# OC_PROT.net
KiCad netlist of a schematic drawn in Altium Designer
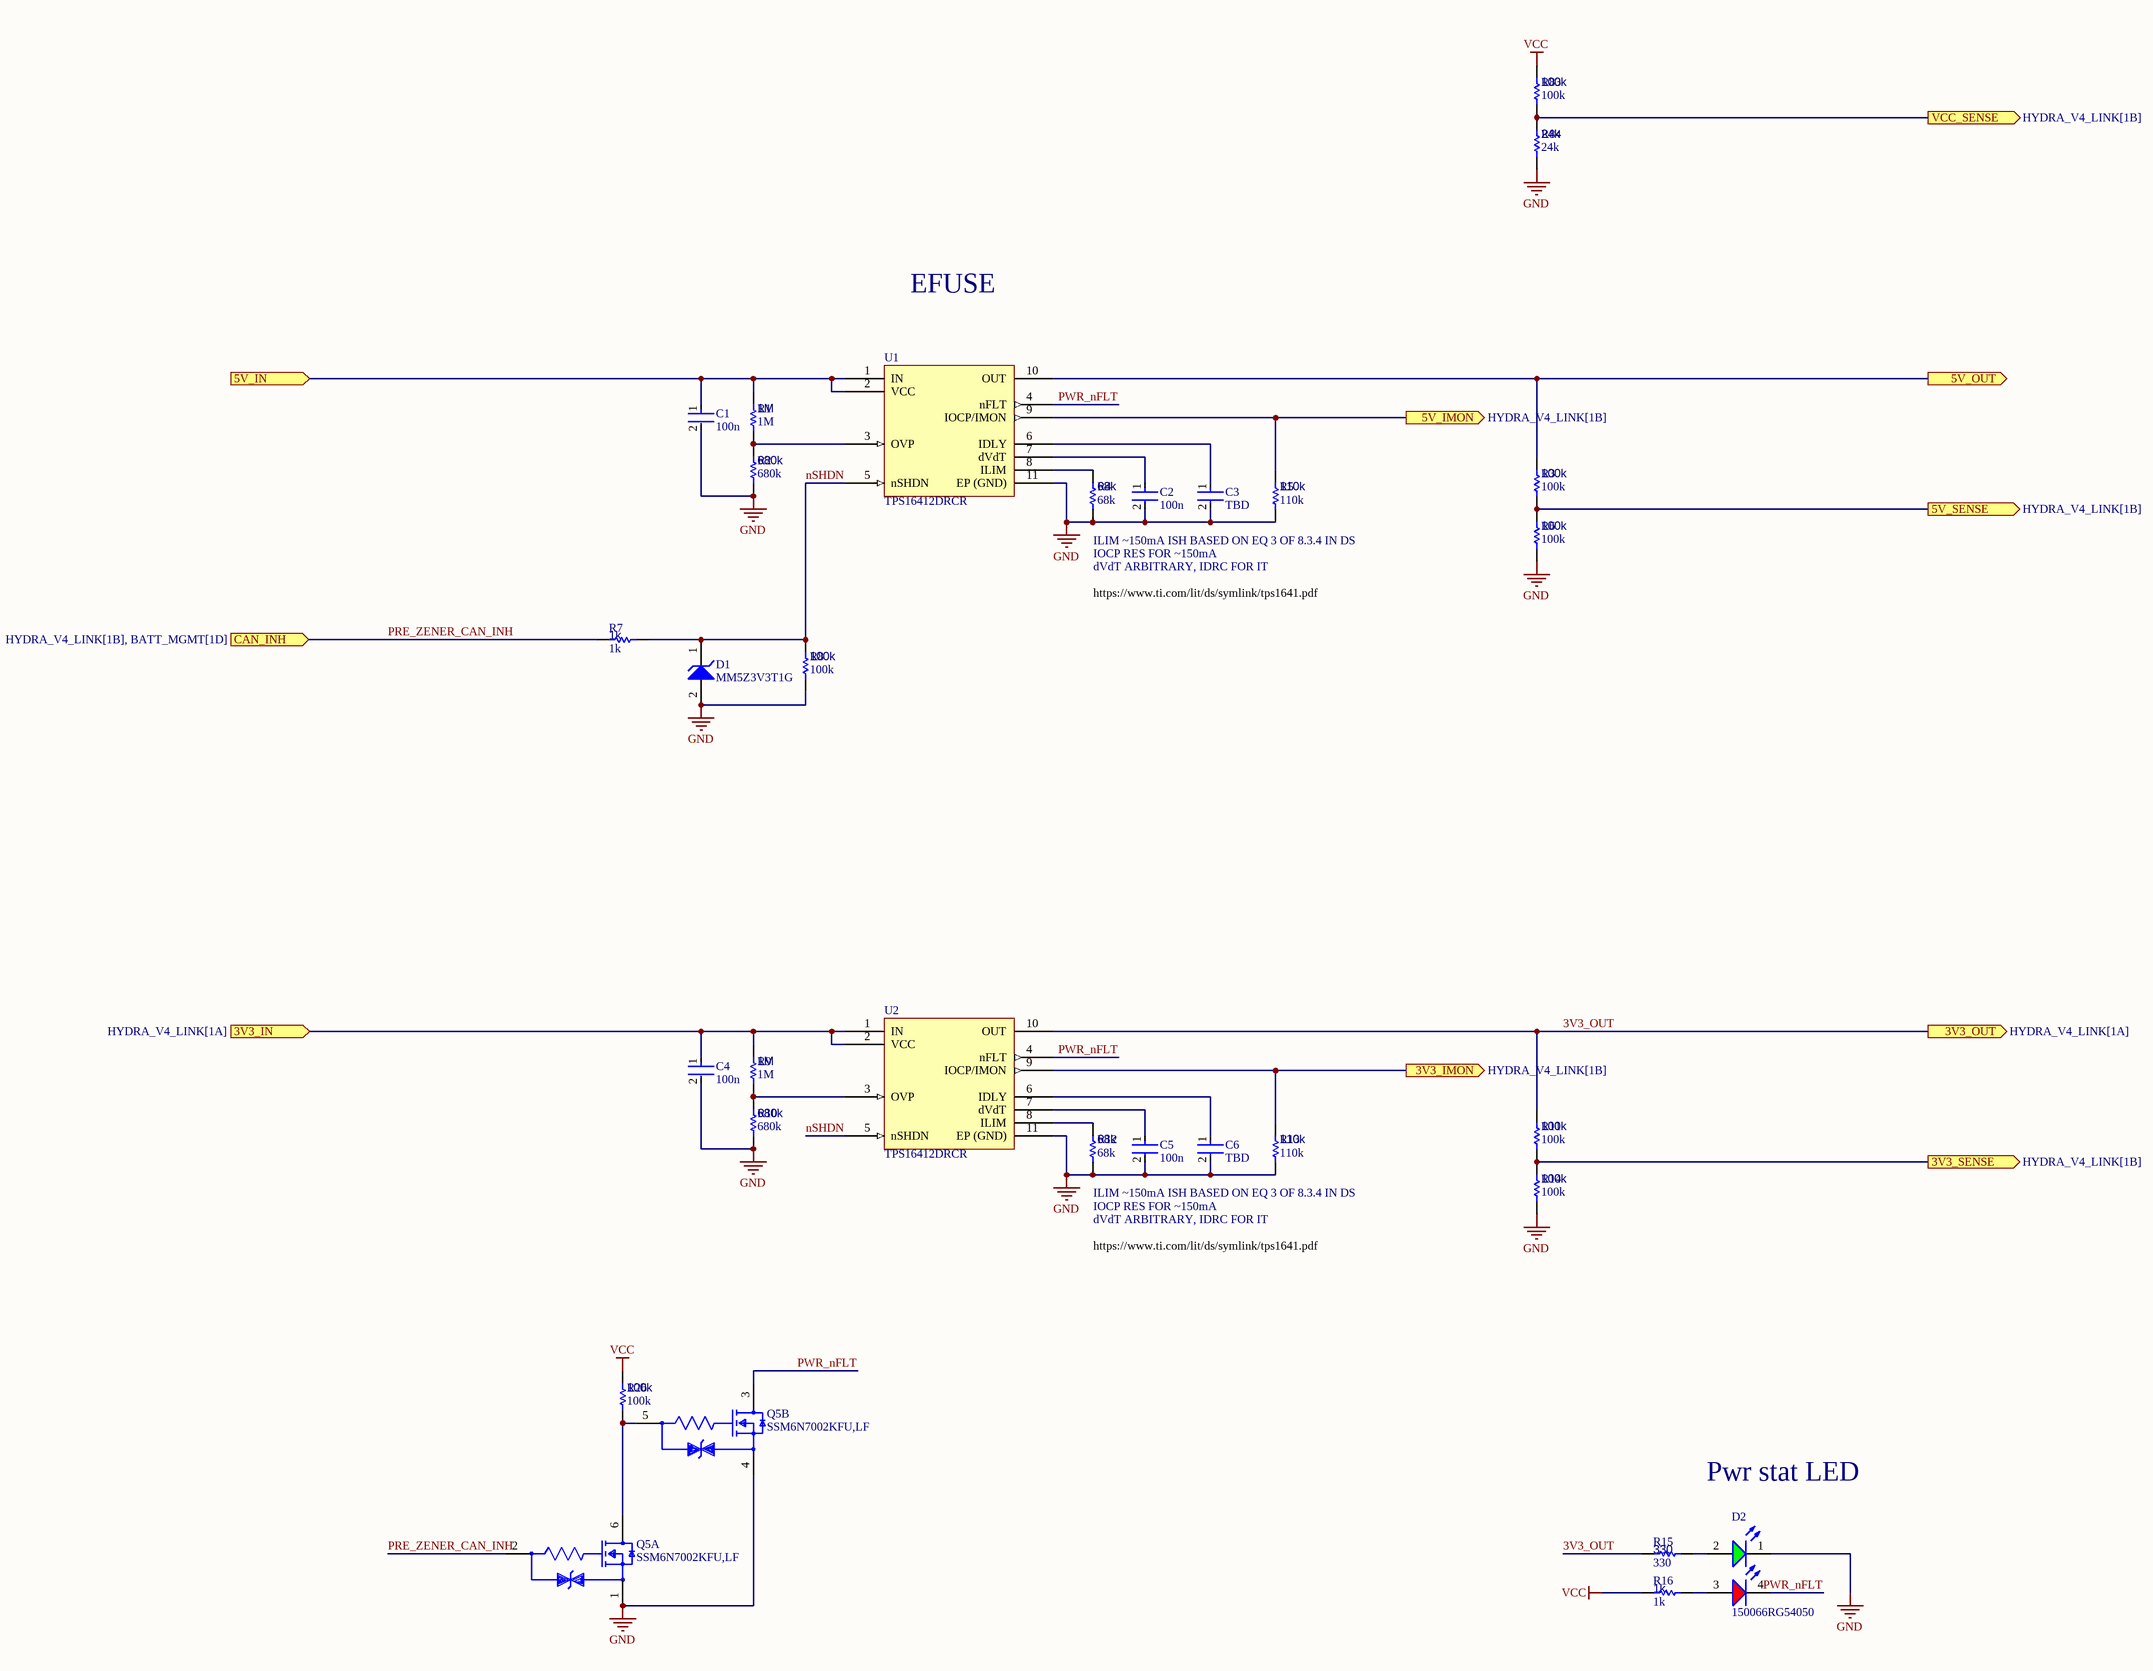
[diagram p0: OC_PROT.SchDoc]

(export (version "E")
  (design (tool "Eeschema 10.0.6"))
  (components
    (comp (ref "C1")
      (value "100n")
      (footprint "FP-0402-L_1_0_0_05-W_0_5-IPC_A")
      (description "LARGE PADS, 0402 CAP, CHANGE COMMENT TO MATCH REAL P/N")
      (libsource (lib "Space Concordia") (part "b4654b650e69147ec39a6b967a45e02"))
    )
    (comp (ref "C2")
      (value "100n")
      (footprint "FP-0402-L_1_0_0_05-W_0_5-IPC_A")
      (description "LARGE PADS, 0402 CAP, CHANGE COMMENT TO MATCH REAL P/N")
      (libsource (lib "Space Concordia") (part "b4654b650e69147ec39a6b967a45e02"))
    )
    (comp (ref "C3")
      (value "TBD")
      (footprint "FP-0402-L_1_0_0_05-W_0_5-IPC_A")
      (description "LARGE PADS, 0402 CAP, CHANGE COMMENT TO MATCH REAL P/N")
      (libsource (lib "Space Concordia") (part "b4654b650e69147ec39a6b967a45e02"))
    )
    (comp (ref "C4")
      (value "100n")
      (footprint "FP-0402-L_1_0_0_05-W_0_5-IPC_A")
      (description "LARGE PADS, 0402 CAP, CHANGE COMMENT TO MATCH REAL P/N")
      (libsource (lib "Space Concordia") (part "b4654b650e69147ec39a6b967a45e02"))
    )
    (comp (ref "C5")
      (value "100n")
      (footprint "FP-0402-L_1_0_0_05-W_0_5-IPC_A")
      (description "LARGE PADS, 0402 CAP, CHANGE COMMENT TO MATCH REAL P/N")
      (libsource (lib "Space Concordia") (part "b4654b650e69147ec39a6b967a45e02"))
    )
    (comp (ref "C6")
      (value "TBD")
      (footprint "FP-0402-L_1_0_0_05-W_0_5-IPC_A")
      (description "LARGE PADS, 0402 CAP, CHANGE COMMENT TO MATCH REAL P/N")
      (libsource (lib "Space Concordia") (part "b4654b650e69147ec39a6b967a45e02"))
    )
    (comp (ref "D1")
      (value "MM5Z3V3T1G")
      (footprint "ONSC-SOD-523-2-502-01_V")
      (description "Zener Voltage Regulator, 500 mW, 2-Pin SOD-523, Pb-Free, Tape and Reel")
      (fields (field (name "MANUFACTURER") "On Semiconductor"))
      (libsource (lib "Altium Content Vault") (part "ONSC-K1A2-2"))
    )
    (comp (ref "D2")
      (value "150066RG54050")
      (footprint "WL-SBCD_0606")
      (description "Led, Red/Grn, 180Mcd/230Mcd, 624Nm/525Nm Rohs Compliant: Yes")
      (fields (field (name "SOURCE") "rgled.SchLib"))
      (libsource (lib "Space Concordia") (part "CMP-004-00034-2"))
    )
    (comp (ref "Q5")
      (value "SSM6N7002KFU,LF")
      (footprint "FP-SSOP6-P-0_65A-MFG")
      (description "Transistor MOSFET Array Dual N-CH 60V 300mA 6-Pin SOT-363 Emboss T/R")
      (libsource (lib "Space Concordia") (part "088aa6ac103fdeebe0d1c52ece6b7b9"))
    )
    (comp (ref "R1")
      (value "1M")
      (footprint "R0603B")
      (description "Resistor")
      (fields (field (name "ALTIUM_VALUE") "1M"))
      (libsource (lib "Space Concordia") (part "Resistor"))
    )
    (comp (ref "R2")
      (value "680k")
      (footprint "R0603B")
      (description "Resistor")
      (fields (field (name "ALTIUM_VALUE") "680k"))
      (libsource (lib "Space Concordia") (part "Resistor"))
    )
    (comp (ref "R3")
      (value "100k")
      (footprint "R0603B")
      (description "Resistor")
      (fields (field (name "ALTIUM_VALUE") "100k"))
      (libsource (lib "Space Concordia") (part "Resistor"))
    )
    (comp (ref "R4")
      (value "68k")
      (footprint "R0603B")
      (description "Resistor")
      (fields (field (name "ALTIUM_VALUE") "68k"))
      (libsource (lib "Space Concordia") (part "Resistor"))
    )
    (comp (ref "R5")
      (value "110k")
      (footprint "R0603B")
      (description "Resistor")
      (fields (field (name "ALTIUM_VALUE") "110k"))
      (libsource (lib "Space Concordia") (part "Resistor"))
    )
    (comp (ref "R6")
      (value "100k")
      (footprint "R0603B")
      (description "Resistor")
      (fields (field (name "ALTIUM_VALUE") "100k"))
      (libsource (lib "Space Concordia") (part "Resistor"))
    )
    (comp (ref "R7")
      (value "1k")
      (footprint "R0603B")
      (description "Resistor")
      (fields (field (name "ALTIUM_VALUE") "1k"))
      (libsource (lib "Space Concordia") (part "Resistor"))
    )
    (comp (ref "R8")
      (value "100k")
      (footprint "R0603B")
      (description "Resistor")
      (fields (field (name "ALTIUM_VALUE") "100k"))
      (libsource (lib "Space Concordia") (part "Resistor"))
    )
    (comp (ref "R9")
      (value "1M")
      (footprint "R0603B")
      (description "Resistor")
      (fields (field (name "ALTIUM_VALUE") "1M"))
      (libsource (lib "Space Concordia") (part "Resistor"))
    )
    (comp (ref "R10")
      (value "680k")
      (footprint "R0603B")
      (description "Resistor")
      (fields (field (name "ALTIUM_VALUE") "680k"))
      (libsource (lib "Space Concordia") (part "Resistor"))
    )
    (comp (ref "R11")
      (value "100k")
      (footprint "R0603B")
      (description "Resistor")
      (fields (field (name "ALTIUM_VALUE") "100k"))
      (libsource (lib "Space Concordia") (part "Resistor"))
    )
    (comp (ref "R12")
      (value "68k")
      (footprint "R0603B")
      (description "Resistor")
      (fields (field (name "ALTIUM_VALUE") "68k"))
      (libsource (lib "Space Concordia") (part "Resistor"))
    )
    (comp (ref "R13")
      (value "110k")
      (footprint "R0603B")
      (description "Resistor")
      (fields (field (name "ALTIUM_VALUE") "110k"))
      (libsource (lib "Space Concordia") (part "Resistor"))
    )
    (comp (ref "R14")
      (value "100k")
      (footprint "R0603B")
      (description "Resistor")
      (fields (field (name "ALTIUM_VALUE") "100k"))
      (libsource (lib "Space Concordia") (part "Resistor"))
    )
    (comp (ref "R15")
      (value "330")
      (footprint "R0603B")
      (description "Resistor")
      (fields (field (name "ALTIUM_VALUE") "330"))
      (libsource (lib "Space Concordia") (part "Resistor"))
    )
    (comp (ref "R16")
      (value "1k")
      (footprint "R0603B")
      (description "Resistor")
      (fields (field (name "ALTIUM_VALUE") "1k"))
      (libsource (lib "Space Concordia") (part "Resistor"))
    )
    (comp (ref "R26")
      (value "100k")
      (footprint "R0603B")
      (description "Resistor")
      (fields (field (name "ALTIUM_VALUE") "100k"))
      (libsource (lib "Space Concordia") (part "Resistor"))
    )
    (comp (ref "R83")
      (value "100k")
      (footprint "R0603B")
      (description "Resistor")
      (fields (field (name "ALTIUM_VALUE") "100k"))
      (libsource (lib "Space Concordia") (part "Resistor"))
    )
    (comp (ref "R84")
      (value "24k")
      (footprint "R0603B")
      (description "Resistor")
      (fields (field (name "ALTIUM_VALUE") "24k"))
      (libsource (lib "Space Concordia") (part "Resistor"))
    )
    (comp (ref "U1")
      (value "TPS16412DRCR")
      (footprint "PSON50P300X100_HS-11N")
      (description "2.7-V to 40-V 152-mΩ 1.8-A eFuse with output power limiting 10-VSON -40 to 125")
      (libsource (lib "Space Concordia") (part "TPS16412DRCR"))
    )
    (comp (ref "U2")
      (value "TPS16412DRCR")
      (footprint "PSON50P300X100_HS-11N")
      (description "2.7-V to 40-V 152-mΩ 1.8-A eFuse with output power limiting 10-VSON -40 to 125")
      (libsource (lib "Space Concordia") (part "TPS16412DRCR"))
    )
  )
  (nets
    (net (code "1") (name "/3V3_IMON") (class "Default")
      (node (ref "R13") (pin "1") (pinfunction "1_1") (pintype "passive"))
      (node (ref "U2") (pin "9") (pinfunction "IOCP/IMON_9") (pintype "output"))
    )
    (net (code "2") (name "/3V3_IN") (class "Default")
      (node (ref "C4") (pin "1") (pinfunction "1_1") (pintype "passive"))
      (node (ref "R9") (pin "1") (pinfunction "1_1") (pintype "passive"))
      (node (ref "U2") (pin "1") (pinfunction "IN_1") (pintype "power_in"))
      (node (ref "U2") (pin "2") (pinfunction "VCC_2") (pintype "power_in"))
    )
    (net (code "3") (name "/3V3_OUT") (class "Default")
      (node (ref "R11") (pin "2") (pinfunction "2_2") (pintype "passive"))
      (node (ref "R15") (pin "1") (pinfunction "1_1") (pintype "passive"))
      (node (ref "U2") (pin "10") (pinfunction "OUT_10") (pintype "power_in"))
    )
    (net (code "4") (name "/3V3_SENSE") (class "Default")
      (node (ref "R11") (pin "1") (pinfunction "1_1") (pintype "passive"))
      (node (ref "R14") (pin "2") (pinfunction "2_2") (pintype "passive"))
    )
    (net (code "5") (name "/5V_IMON") (class "Default")
      (node (ref "R5") (pin "1") (pinfunction "1_1") (pintype "passive"))
      (node (ref "U1") (pin "9") (pinfunction "IOCP/IMON_9") (pintype "output"))
    )
    (net (code "6") (name "/5V_IN") (class "Default")
      (node (ref "C1") (pin "1") (pinfunction "1_1") (pintype "passive"))
      (node (ref "R1") (pin "1") (pinfunction "1_1") (pintype "passive"))
      (node (ref "U1") (pin "1") (pinfunction "IN_1") (pintype "power_in"))
      (node (ref "U1") (pin "2") (pinfunction "VCC_2") (pintype "power_in"))
    )
    (net (code "7") (name "/5V_OUT") (class "Default")
      (node (ref "R3") (pin "2") (pinfunction "2_2") (pintype "passive"))
      (node (ref "U1") (pin "10") (pinfunction "OUT_10") (pintype "power_in"))
    )
    (net (code "8") (name "/5V_SENSE") (class "Default")
      (node (ref "R3") (pin "1") (pinfunction "1_1") (pintype "passive"))
      (node (ref "R6") (pin "2") (pinfunction "2_2") (pintype "passive"))
    )
    (net (code "9") (name "/PRE_ZENER_CAN_INH") (class "Default")
      (node (ref "Q5") (pin "2") (pinfunction "Gate1_2") (pintype "passive"))
      (node (ref "R7") (pin "2") (pinfunction "2_2") (pintype "passive"))
    )
    (net (code "10") (name "/PWR_nFLT") (class "Default")
      (node (ref "D2") (pin "4") (pinfunction "K_4") (pintype "passive"))
      (node (ref "Q5") (pin "3") (pinfunction "Drain2_3") (pintype "passive"))
      (node (ref "U1") (pin "4") (pinfunction "nFLT_4") (pintype "output"))
      (node (ref "U2") (pin "4") (pinfunction "nFLT_4") (pintype "output"))
    )
    (net (code "11") (name "/VCC_SENSE") (class "Default")
      (node (ref "R83") (pin "1") (pinfunction "1_1") (pintype "passive"))
      (node (ref "R84") (pin "2") (pinfunction "2_2") (pintype "passive"))
    )
    (net (code "12") (name "/nSHDN") (class "Default")
      (node (ref "D1") (pin "1") (pinfunction "K_1") (pintype "passive"))
      (node (ref "R7") (pin "1") (pinfunction "1_1") (pintype "passive"))
      (node (ref "R8") (pin "2") (pinfunction "2_2") (pintype "passive"))
      (node (ref "U1") (pin "5") (pinfunction "nSHDN_5") (pintype "input"))
      (node (ref "U2") (pin "5") (pinfunction "nSHDN_5") (pintype "input"))
    )
    (net (code "13") (name "GND") (class "Default")
      (node (ref "C1") (pin "2") (pinfunction "2_2") (pintype "passive"))
      (node (ref "C2") (pin "2") (pinfunction "2_2") (pintype "passive"))
      (node (ref "C3") (pin "2") (pinfunction "2_2") (pintype "passive"))
      (node (ref "C4") (pin "2") (pinfunction "2_2") (pintype "passive"))
      (node (ref "C5") (pin "2") (pinfunction "2_2") (pintype "passive"))
      (node (ref "C6") (pin "2") (pinfunction "2_2") (pintype "passive"))
      (node (ref "D1") (pin "2") (pinfunction "A_2") (pintype "passive"))
      (node (ref "D2") (pin "1") (pinfunction "K_1") (pintype "passive"))
      (node (ref "Q5") (pin "1") (pinfunction "Source1_1") (pintype "passive"))
      (node (ref "Q5") (pin "4") (pinfunction "Source2_4") (pintype "passive"))
      (node (ref "R10") (pin "2") (pinfunction "2_2") (pintype "passive"))
      (node (ref "R12") (pin "2") (pinfunction "2_2") (pintype "passive"))
      (node (ref "R13") (pin "2") (pinfunction "2_2") (pintype "passive"))
      (node (ref "R14") (pin "1") (pinfunction "1_1") (pintype "passive"))
      (node (ref "R2") (pin "2") (pinfunction "2_2") (pintype "passive"))
      (node (ref "R4") (pin "2") (pinfunction "2_2") (pintype "passive"))
      (node (ref "R5") (pin "2") (pinfunction "2_2") (pintype "passive"))
      (node (ref "R6") (pin "1") (pinfunction "1_1") (pintype "passive"))
      (node (ref "R8") (pin "1") (pinfunction "1_1") (pintype "passive"))
      (node (ref "R84") (pin "1") (pinfunction "1_1") (pintype "passive"))
      (node (ref "U1") (pin "11") (pinfunction "EP_(GND)_11") (pintype "power_in"))
      (node (ref "U2") (pin "11") (pinfunction "EP_(GND)_11") (pintype "power_in"))
    )
    (net (code "14") (name "Net-(D2-A-Pad2)") (class "Default")
      (node (ref "D2") (pin "2") (pinfunction "A_2") (pintype "passive"))
      (node (ref "R15") (pin "2") (pinfunction "2_2") (pintype "passive"))
    )
    (net (code "15") (name "Net-(D2-A-Pad3)") (class "Default")
      (node (ref "D2") (pin "3") (pinfunction "A_3") (pintype "passive"))
      (node (ref "R16") (pin "2") (pinfunction "2_2") (pintype "passive"))
    )
    (net (code "16") (name "Net-(Q5A-Drain1)") (class "Default")
      (node (ref "Q5") (pin "5") (pinfunction "Gate2_5") (pintype "passive"))
      (node (ref "Q5") (pin "6") (pinfunction "Drain1_6") (pintype "passive"))
      (node (ref "R26") (pin "2") (pinfunction "2_2") (pintype "passive"))
    )
    (net (code "17") (name "Net-(U1-IDLY)") (class "Default")
      (node (ref "C3") (pin "1") (pinfunction "1_1") (pintype "passive"))
      (node (ref "U1") (pin "6") (pinfunction "IDLY_6") (pintype "passive"))
    )
    (net (code "18") (name "Net-(U1-ILIM)") (class "Default")
      (node (ref "R4") (pin "1") (pinfunction "1_1") (pintype "passive"))
      (node (ref "U1") (pin "8") (pinfunction "ILIM_8") (pintype "passive"))
    )
    (net (code "19") (name "Net-(U1-OVP)") (class "Default")
      (node (ref "R1") (pin "2") (pinfunction "2_2") (pintype "passive"))
      (node (ref "R2") (pin "1") (pinfunction "1_1") (pintype "passive"))
      (node (ref "U1") (pin "3") (pinfunction "OVP_3") (pintype "input"))
    )
    (net (code "20") (name "Net-(U1-dVdT)") (class "Default")
      (node (ref "C2") (pin "1") (pinfunction "1_1") (pintype "passive"))
      (node (ref "U1") (pin "7") (pinfunction "dVdT_7") (pintype "passive"))
    )
    (net (code "21") (name "Net-(U2-IDLY)") (class "Default")
      (node (ref "C6") (pin "1") (pinfunction "1_1") (pintype "passive"))
      (node (ref "U2") (pin "6") (pinfunction "IDLY_6") (pintype "passive"))
    )
    (net (code "22") (name "Net-(U2-ILIM)") (class "Default")
      (node (ref "R12") (pin "1") (pinfunction "1_1") (pintype "passive"))
      (node (ref "U2") (pin "8") (pinfunction "ILIM_8") (pintype "passive"))
    )
    (net (code "23") (name "Net-(U2-OVP)") (class "Default")
      (node (ref "R10") (pin "1") (pinfunction "1_1") (pintype "passive"))
      (node (ref "R9") (pin "2") (pinfunction "2_2") (pintype "passive"))
      (node (ref "U2") (pin "3") (pinfunction "OVP_3") (pintype "input"))
    )
    (net (code "24") (name "Net-(U2-dVdT)") (class "Default")
      (node (ref "C5") (pin "1") (pinfunction "1_1") (pintype "passive"))
      (node (ref "U2") (pin "7") (pinfunction "dVdT_7") (pintype "passive"))
    )
    (net (code "25") (name "VCC") (class "Default")
      (node (ref "R16") (pin "1") (pinfunction "1_1") (pintype "passive"))
      (node (ref "R26") (pin "1") (pinfunction "1_1") (pintype "passive"))
      (node (ref "R83") (pin "2") (pinfunction "2_2") (pintype "passive"))
    )
  )
)
